# GarageDoorController-v10.net
KiCad netlist of a schematic drawn in EAGLE
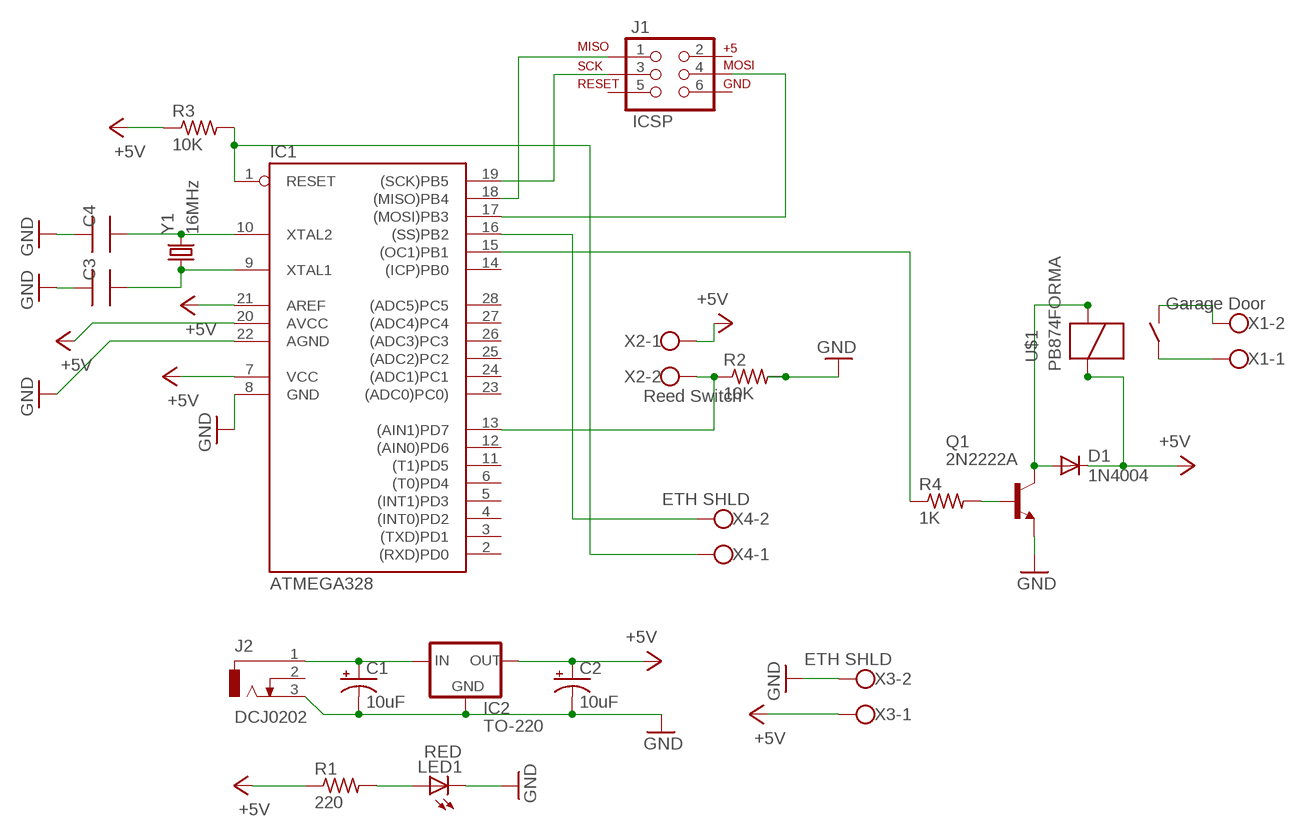
[diagram p0: schematic, sheet 1]

(export (version "E")
  (design (tool "Eeschema 10.0.6"))
  (components
    (comp (ref "C1")
      (value "10uF")
      (footprint "eagle-import:E2-5")
      (libsource (lib "eagle-import") (part "CPOL-USE2-5"))
    )
    (comp (ref "C2")
      (value "10uF")
      (footprint "eagle-import:E2-5")
      (libsource (lib "eagle-import") (part "CPOL-USE2-5"))
    )
    (comp (ref "C3")
      (value "1440PH")
      (footprint "eagle-import:1440PH")
      (libsource (lib "eagle-import") (part "1440PH"))
    )
    (comp (ref "C4")
      (value "1440PH")
      (footprint "eagle-import:1440PH")
      (libsource (lib "eagle-import") (part "1440PH"))
    )
    (comp (ref "D1")
      (value "1N4004")
      (footprint "eagle-import:DO41-10")
      (libsource (lib "eagle-import") (part "1N4004"))
    )
    (comp (ref "IC1")
      (value "ATMEGA328")
      (footprint "eagle-import:DIL28-3")
      (libsource (lib "eagle-import") (part "AT90S4433P"))
    )
    (comp (ref "IC2")
      (value "TO-220")
      (footprint "eagle-import:TO-220-ALT")
      (libsource (lib "eagle-import") (part "V_REG_78XX-TO-220"))
    )
    (comp (ref "J1")
      (value "ICSP")
      (footprint "eagle-import:2X3")
      (libsource (lib "eagle-import") (part "AVR_SPI_PRG_6PTH"))
    )
    (comp (ref "J2")
      (value "DCJ0202")
      (footprint "eagle-import:DCJ0202")
      (libsource (lib "eagle-import") (part "DCJ0202"))
    )
    (comp (ref "LED1")
      (value "RED")
      (footprint "eagle-import:LED5MM")
      (libsource (lib "eagle-import") (part "LED5MM"))
    )
    (comp (ref "Q1")
      (value "2N2222A")
      (footprint "eagle-import:TO18")
      (libsource (lib "eagle-import") (part "2N2222A"))
    )
    (comp (ref "R1")
      (value "220")
      (footprint "eagle-import:0204_7")
      (libsource (lib "eagle-import") (part "R-US_0204/7"))
    )
    (comp (ref "R2")
      (value "10K")
      (footprint "eagle-import:0204_7")
      (libsource (lib "eagle-import") (part "R-US_0204/7"))
    )
    (comp (ref "R3")
      (value "10K")
      (footprint "eagle-import:0204_7")
      (libsource (lib "eagle-import") (part "R-US_0204/7"))
    )
    (comp (ref "R4")
      (value "1K")
      (footprint "eagle-import:0204_7")
      (libsource (lib "eagle-import") (part "R-US_0204/7"))
    )
    (comp (ref "U$1")
      (value "PB874FORMA")
      (footprint "eagle-import:PB874")
      (libsource (lib "eagle-import") (part "PB874FORMA"))
    )
    (comp (ref "X1")
      (value "Garage Door")
      (footprint "eagle-import:W237-102")
      (fields (field (name "MPN") "237-102"))
      (libsource (lib "eagle-import") (part "W237-102"))
    )
    (comp (ref "X2")
      (value "Reed Switch")
      (footprint "eagle-import:W237-102")
      (fields (field (name "MPN") "237-102"))
      (libsource (lib "eagle-import") (part "W237-102"))
    )
    (comp (ref "X3")
      (value "ETH SHLD")
      (footprint "eagle-import:W237-102")
      (fields (field (name "MPN") "237-102"))
      (libsource (lib "eagle-import") (part "W237-102"))
    )
    (comp (ref "X4")
      (value "ETH SHLD")
      (footprint "eagle-import:W237-102")
      (fields (field (name "MPN") "237-102"))
      (libsource (lib "eagle-import") (part "W237-102"))
    )
    (comp (ref "Y1")
      (value "16MHz")
      (footprint "eagle-import:HC49US")
      (libsource (lib "eagle-import") (part "CRYSTALHC49US"))
    )
  )
  (nets
    (net (code "1") (name "+5V") (class "Default")
      (node (ref "C2") (pin "+") (pinfunction "+_+") (pintype "passive"))
      (node (ref "D1") (pin "C") (pinfunction "C_C") (pintype "passive"))
      (node (ref "IC1") (pin "20") (pinfunction "AVCC_20") (pintype "power_in"))
      (node (ref "IC1") (pin "21") (pinfunction "AREF_21") (pintype "passive"))
      (node (ref "IC1") (pin "7") (pinfunction "VCC_7") (pintype "power_in"))
      (node (ref "IC2") (pin "OUT") (pinfunction "OUT_OUT") (pintype "output"))
      (node (ref "R1") (pin "1") (pinfunction "1_1") (pintype "passive"))
      (node (ref "R3") (pin "1") (pinfunction "1_1") (pintype "passive"))
      (node (ref "U$1") (pin "2") (pinfunction "P$2_2") (pintype "bidirectional"))
      (node (ref "X2") (pin "1") (pinfunction "KL_1") (pintype "passive"))
      (node (ref "X3") (pin "1") (pinfunction "KL_1") (pintype "passive"))
    )
    (net (code "2") (name "GND") (class "Default")
      (node (ref "C1") (pin "-") (pinfunction "-_-") (pintype "passive"))
      (node (ref "C2") (pin "-") (pinfunction "-_-") (pintype "passive"))
      (node (ref "C3") (pin "1") (pinfunction "P$1_1") (pintype "passive"))
      (node (ref "C4") (pin "1") (pinfunction "P$1_1") (pintype "passive"))
      (node (ref "IC1") (pin "22") (pinfunction "AGND_22") (pintype "power_in"))
      (node (ref "IC1") (pin "8") (pinfunction "GND_8") (pintype "power_in"))
      (node (ref "IC2") (pin "GND") (pinfunction "GND_GND") (pintype "input"))
      (node (ref "J2") (pin "3") (pinfunction "3_3") (pintype "passive"))
      (node (ref "LED1") (pin "K") (pinfunction "C_K") (pintype "passive"))
      (node (ref "Q1") (pin "1") (pinfunction "E_1") (pintype "passive"))
      (node (ref "R2") (pin "2") (pinfunction "2_2") (pintype "passive"))
      (node (ref "X3") (pin "2") (pinfunction "KL_2") (pintype "passive"))
    )
    (net (code "3") (name "Net-(C1-Pad+)") (class "Default")
      (node (ref "C1") (pin "+") (pinfunction "+_+") (pintype "passive"))
      (node (ref "IC2") (pin "IN") (pinfunction "IN_IN") (pintype "input"))
      (node (ref "J2") (pin "1") (pinfunction "1_1") (pintype "passive"))
    )
    (net (code "4") (name "Net-(C3-P$2)") (class "Default")
      (node (ref "C3") (pin "2") (pinfunction "P$2_2") (pintype "passive"))
      (node (ref "IC1") (pin "9") (pinfunction "XTAL1_9") (pintype "bidirectional"))
      (node (ref "Y1") (pin "1") (pinfunction "1_1") (pintype "passive"))
    )
    (net (code "5") (name "Net-(C4-P$2)") (class "Default")
      (node (ref "C4") (pin "2") (pinfunction "P$2_2") (pintype "passive"))
      (node (ref "IC1") (pin "10") (pinfunction "XTAL2_10") (pintype "bidirectional"))
      (node (ref "Y1") (pin "2") (pinfunction "2_2") (pintype "passive"))
    )
    (net (code "6") (name "Net-(IC1-(AIN1)PD7)") (class "Default")
      (node (ref "IC1") (pin "13") (pinfunction "(AIN1)PD7_13") (pintype "bidirectional"))
      (node (ref "R2") (pin "1") (pinfunction "1_1") (pintype "passive"))
      (node (ref "X2") (pin "2") (pinfunction "KL_2") (pintype "passive"))
    )
    (net (code "7") (name "Net-(IC1-(MISO)PB4)") (class "Default")
      (node (ref "IC1") (pin "18") (pinfunction "(MISO)PB4_18") (pintype "bidirectional"))
      (node (ref "J1") (pin "1") (pinfunction "1_1") (pintype "passive"))
    )
    (net (code "8") (name "Net-(IC1-(MOSI)PB3)") (class "Default")
      (node (ref "IC1") (pin "17") (pinfunction "(MOSI)PB3_17") (pintype "bidirectional"))
      (node (ref "J1") (pin "4") (pinfunction "4_4") (pintype "passive"))
    )
    (net (code "9") (name "Net-(IC1-(OC1)PB1)") (class "Default")
      (node (ref "IC1") (pin "15") (pinfunction "(OC1)PB1_15") (pintype "bidirectional"))
      (node (ref "R4") (pin "1") (pinfunction "1_1") (pintype "passive"))
    )
    (net (code "10") (name "Net-(IC1-(SCK)PB5)") (class "Default")
      (node (ref "IC1") (pin "19") (pinfunction "(SCK)PB5_19") (pintype "bidirectional"))
      (node (ref "J1") (pin "3") (pinfunction "3_3") (pintype "passive"))
    )
    (net (code "11") (name "Net-(IC1-(SS)PB2)") (class "Default")
      (node (ref "IC1") (pin "16") (pinfunction "(SS)PB2_16") (pintype "bidirectional"))
      (node (ref "X4") (pin "2") (pinfunction "KL_2") (pintype "passive"))
    )
    (net (code "12") (name "Net-(IC1-RESET)") (class "Default")
      (node (ref "IC1") (pin "1") (pinfunction "RESET_1") (pintype "input"))
      (node (ref "R3") (pin "2") (pinfunction "2_2") (pintype "passive"))
      (node (ref "X4") (pin "1") (pinfunction "KL_1") (pintype "passive"))
    )
    (net (code "13") (name "Net-(LED1-PadA)") (class "Default")
      (node (ref "LED1") (pin "A") (pinfunction "A_A") (pintype "passive"))
      (node (ref "R1") (pin "2") (pinfunction "2_2") (pintype "passive"))
    )
    (net (code "14") (name "Net-(Q1-B)") (class "Default")
      (node (ref "Q1") (pin "2") (pinfunction "B_2") (pintype "passive"))
      (node (ref "R4") (pin "2") (pinfunction "2_2") (pintype "passive"))
    )
    (net (code "15") (name "Net-(Q1-C)") (class "Default")
      (node (ref "D1") (pin "A") (pinfunction "A_A") (pintype "passive"))
      (node (ref "Q1") (pin "3") (pinfunction "C_3") (pintype "passive"))
      (node (ref "U$1") (pin "1") (pinfunction "P$1_1") (pintype "bidirectional"))
    )
    (net (code "16") (name "Net-(U$1-P$3)") (class "Default")
      (node (ref "U$1") (pin "4") (pinfunction "P$3_4") (pintype "passive"))
      (node (ref "X1") (pin "2") (pinfunction "KL_2") (pintype "passive"))
    )
    (net (code "17") (name "Net-(U$1-P$4)") (class "Default")
      (node (ref "U$1") (pin "3") (pinfunction "P$4_3") (pintype "passive"))
      (node (ref "X1") (pin "1") (pinfunction "KL_1") (pintype "passive"))
    )
    (net (code "18") (name "unconnected-(IC1-(ADC0)PC0)-Pad23)") (class "Default")
      (node (ref "IC1") (pin "23") (pinfunction "(ADC0)PC0)_23") (pintype "bidirectional"))
    )
    (net (code "19") (name "unconnected-(IC1-(ADC1)PC1-Pad24)") (class "Default")
      (node (ref "IC1") (pin "24") (pinfunction "(ADC1)PC1_24") (pintype "bidirectional"))
    )
    (net (code "20") (name "unconnected-(IC1-(ADC2)PC2-Pad25)") (class "Default")
      (node (ref "IC1") (pin "25") (pinfunction "(ADC2)PC2_25") (pintype "bidirectional"))
    )
    (net (code "21") (name "unconnected-(IC1-(ADC3)PC3-Pad26)") (class "Default")
      (node (ref "IC1") (pin "26") (pinfunction "(ADC3)PC3_26") (pintype "bidirectional"))
    )
    (net (code "22") (name "unconnected-(IC1-(ADC4)PC4-Pad27)") (class "Default")
      (node (ref "IC1") (pin "27") (pinfunction "(ADC4)PC4_27") (pintype "bidirectional"))
    )
    (net (code "23") (name "unconnected-(IC1-(ADC5)PC5-Pad28)") (class "Default")
      (node (ref "IC1") (pin "28") (pinfunction "(ADC5)PC5_28") (pintype "bidirectional"))
    )
    (net (code "24") (name "unconnected-(IC1-(AIN0)PD6-Pad12)") (class "Default")
      (node (ref "IC1") (pin "12") (pinfunction "(AIN0)PD6_12") (pintype "bidirectional"))
    )
    (net (code "25") (name "unconnected-(IC1-(ICP)PB0-Pad14)") (class "Default")
      (node (ref "IC1") (pin "14") (pinfunction "(ICP)PB0_14") (pintype "bidirectional"))
    )
    (net (code "26") (name "unconnected-(IC1-(INT0)PD2-Pad4)") (class "Default")
      (node (ref "IC1") (pin "4") (pinfunction "(INT0)PD2_4") (pintype "bidirectional"))
    )
    (net (code "27") (name "unconnected-(IC1-(INT1)PD3-Pad5)") (class "Default")
      (node (ref "IC1") (pin "5") (pinfunction "(INT1)PD3_5") (pintype "bidirectional"))
    )
    (net (code "28") (name "unconnected-(IC1-(RXD)PD0-Pad2)") (class "Default")
      (node (ref "IC1") (pin "2") (pinfunction "(RXD)PD0_2") (pintype "bidirectional"))
    )
    (net (code "29") (name "unconnected-(IC1-(T0)PD4-Pad6)") (class "Default")
      (node (ref "IC1") (pin "6") (pinfunction "(T0)PD4_6") (pintype "bidirectional"))
    )
    (net (code "30") (name "unconnected-(IC1-(T1)PD5-Pad11)") (class "Default")
      (node (ref "IC1") (pin "11") (pinfunction "(T1)PD5_11") (pintype "bidirectional"))
    )
    (net (code "31") (name "unconnected-(IC1-(TXD)PD1-Pad3)") (class "Default")
      (node (ref "IC1") (pin "3") (pinfunction "(TXD)PD1_3") (pintype "bidirectional"))
    )
    (net (code "32") (name "unconnected-(J1-Pad2)") (class "Default")
      (node (ref "J1") (pin "2") (pinfunction "2_2") (pintype "passive"))
    )
    (net (code "33") (name "unconnected-(J1-Pad5)") (class "Default")
      (node (ref "J1") (pin "5") (pinfunction "5_5") (pintype "passive"))
    )
    (net (code "34") (name "unconnected-(J1-Pad6)") (class "Default")
      (node (ref "J1") (pin "6") (pinfunction "6_6") (pintype "passive"))
    )
    (net (code "35") (name "unconnected-(J2-Pad2)") (class "Default")
      (node (ref "J2") (pin "2") (pinfunction "2_2") (pintype "passive"))
    )
  )
)
